# senproj_final.net
KiCad netlist of a schematic drawn in EAGLE
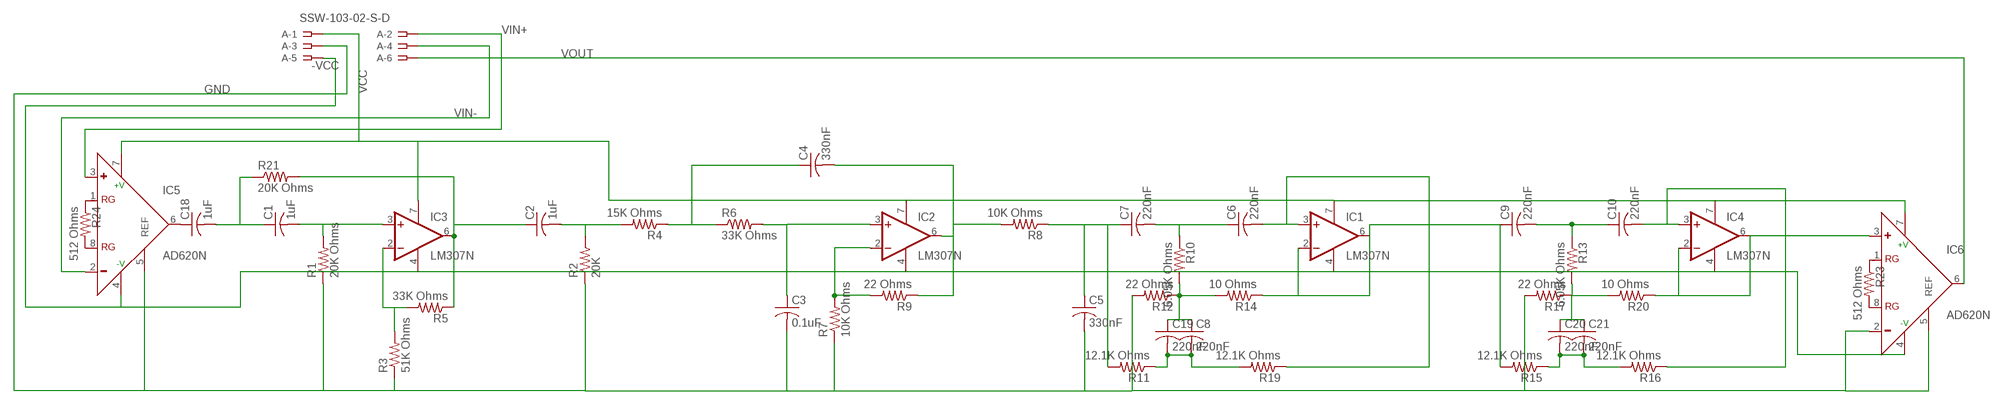
[diagram p0: schematic, sheet 1]

(export (version "E")
  (design (tool "Eeschema 10.0.6"))
  (components
    (comp (ref "A")
      (value "SSW-103-02-S-D")
      (footprint "eagle-import:SSW-103-02-S-D")
      (libsource (lib "eagle-import") (part "SSW-103-02-S-D"))
    )
    (comp (ref "C1")
      (value "1uF")
      (footprint "eagle-import:C150-054X183")
      (libsource (lib "eagle-import") (part "C-US150-054X183"))
    )
    (comp (ref "C2")
      (value "1uF")
      (footprint "eagle-import:C150-054X183")
      (libsource (lib "eagle-import") (part "C-US150-054X183"))
    )
    (comp (ref "C3")
      (value "0.1uF")
      (footprint "eagle-import:C075-032X103")
      (libsource (lib "eagle-import") (part "C-US075-032X103"))
    )
    (comp (ref "C4")
      (value "330nF")
      (footprint "eagle-import:C102-043X133")
      (libsource (lib "eagle-import") (part "C-US102-043X133"))
    )
    (comp (ref "C5")
      (value "330nF")
      (footprint "eagle-import:C102-043X133")
      (libsource (lib "eagle-import") (part "C-US102-043X133"))
    )
    (comp (ref "C6")
      (value "220nF")
      (footprint "eagle-import:C050-024X044")
      (libsource (lib "eagle-import") (part "C-US050-024X044"))
    )
    (comp (ref "C7")
      (value "220nF")
      (footprint "eagle-import:C050-024X044")
      (libsource (lib "eagle-import") (part "C-US050-024X044"))
    )
    (comp (ref "C8")
      (value "220nF")
      (footprint "eagle-import:C050-024X044")
      (libsource (lib "eagle-import") (part "C-US050-024X044"))
    )
    (comp (ref "C9")
      (value "220nF")
      (footprint "eagle-import:C050-024X044")
      (libsource (lib "eagle-import") (part "C-US050-024X044"))
    )
    (comp (ref "C10")
      (value "220nF")
      (footprint "eagle-import:C050-024X044")
      (libsource (lib "eagle-import") (part "C-US050-024X044"))
    )
    (comp (ref "C18")
      (value "1uF")
      (footprint "eagle-import:C150-054X183")
      (libsource (lib "eagle-import") (part "C-US150-054X183"))
    )
    (comp (ref "C19")
      (value "220nF")
      (footprint "eagle-import:C050-024X044")
      (libsource (lib "eagle-import") (part "C-US050-024X044"))
    )
    (comp (ref "C20")
      (value "220nF")
      (footprint "eagle-import:C050-024X044")
      (libsource (lib "eagle-import") (part "C-US050-024X044"))
    )
    (comp (ref "C21")
      (value "220nF")
      (footprint "eagle-import:C050-024X044")
      (libsource (lib "eagle-import") (part "C-US050-024X044"))
    )
    (comp (ref "IC1")
      (value "LM307N")
      (footprint "eagle-import:DIL08")
      (libsource (lib "eagle-import") (part "LM307N"))
    )
    (comp (ref "IC2")
      (value "LM307N")
      (footprint "eagle-import:DIL08")
      (libsource (lib "eagle-import") (part "LM307N"))
    )
    (comp (ref "IC3")
      (value "LM307N")
      (footprint "eagle-import:DIL08")
      (libsource (lib "eagle-import") (part "LM307N"))
    )
    (comp (ref "IC4")
      (value "LM307N")
      (footprint "eagle-import:DIL08")
      (libsource (lib "eagle-import") (part "LM307N"))
    )
    (comp (ref "IC5")
      (value "AD620N")
      (footprint "eagle-import:DIL08")
      (fields (field (name "MF") "ALTERA CORPORATION") (field (name "MPN") "AD620AN"))
      (libsource (lib "eagle-import") (part "AD620N"))
    )
    (comp (ref "IC6")
      (value "AD620N")
      (footprint "eagle-import:DIL08")
      (fields (field (name "MF") "ALTERA CORPORATION") (field (name "MPN") "AD620AN"))
      (libsource (lib "eagle-import") (part "AD620N"))
    )
    (comp (ref "R1")
      (value "20K Ohms")
      (footprint "eagle-import:0204_7")
      (libsource (lib "eagle-import") (part "R-US_0204/7"))
    )
    (comp (ref "R2")
      (value "20K")
      (footprint "eagle-import:0204_7")
      (libsource (lib "eagle-import") (part "R-US_0204/7"))
    )
    (comp (ref "R3")
      (value "51K Ohms")
      (footprint "eagle-import:0204_7")
      (libsource (lib "eagle-import") (part "R-US_0204/7"))
    )
    (comp (ref "R4")
      (value "15K Ohms")
      (footprint "eagle-import:0204_7")
      (libsource (lib "eagle-import") (part "R-US_0204/7"))
    )
    (comp (ref "R5")
      (value "33K Ohms")
      (footprint "eagle-import:0204_7")
      (libsource (lib "eagle-import") (part "R-US_0204/7"))
    )
    (comp (ref "R6")
      (value "33K Ohms")
      (footprint "eagle-import:0204_7")
      (libsource (lib "eagle-import") (part "R-US_0204/7"))
    )
    (comp (ref "R7")
      (value "10K Ohms")
      (footprint "eagle-import:0204_7")
      (libsource (lib "eagle-import") (part "R-US_0204/7"))
    )
    (comp (ref "R8")
      (value "10K Ohms")
      (footprint "eagle-import:0204_7")
      (libsource (lib "eagle-import") (part "R-US_0204/7"))
    )
    (comp (ref "R9")
      (value "22 Ohms")
      (footprint "eagle-import:0204_7")
      (libsource (lib "eagle-import") (part "R-US_0204/7"))
    )
    (comp (ref "R10")
      (value "6.05K Ohms")
      (footprint "eagle-import:0204_7")
      (libsource (lib "eagle-import") (part "R-US_0204/7"))
    )
    (comp (ref "R11")
      (value "12.1K Ohms")
      (footprint "eagle-import:0204_7")
      (libsource (lib "eagle-import") (part "R-US_0204/7"))
    )
    (comp (ref "R12")
      (value "22 Ohms")
      (footprint "eagle-import:0204_7")
      (libsource (lib "eagle-import") (part "R-US_0204/7"))
    )
    (comp (ref "R13")
      (value "6.05K Ohms")
      (footprint "eagle-import:0204_7")
      (libsource (lib "eagle-import") (part "R-US_0204/7"))
    )
    (comp (ref "R14")
      (value "10 Ohms")
      (footprint "eagle-import:0204_7")
      (libsource (lib "eagle-import") (part "R-US_0204/7"))
    )
    (comp (ref "R15")
      (value "12.1K Ohms")
      (footprint "eagle-import:0204_7")
      (libsource (lib "eagle-import") (part "R-US_0204/7"))
    )
    (comp (ref "R16")
      (value "12.1K Ohms")
      (footprint "eagle-import:0204_7")
      (libsource (lib "eagle-import") (part "R-US_0204/7"))
    )
    (comp (ref "R17")
      (value "22 Ohms")
      (footprint "eagle-import:0204_7")
      (libsource (lib "eagle-import") (part "R-US_0204/7"))
    )
    (comp (ref "R19")
      (value "12.1K Ohms")
      (footprint "eagle-import:0204_7")
      (libsource (lib "eagle-import") (part "R-US_0204/7"))
    )
    (comp (ref "R20")
      (value "10 Ohms")
      (footprint "eagle-import:0204_7")
      (libsource (lib "eagle-import") (part "R-US_0204/7"))
    )
    (comp (ref "R21")
      (value "20K Ohms")
      (footprint "eagle-import:0204_7")
      (libsource (lib "eagle-import") (part "R-US_0204/7"))
    )
    (comp (ref "R23")
      (value "512 Ohms")
      (footprint "eagle-import:0204_7")
      (libsource (lib "eagle-import") (part "R-US_0204/7"))
    )
    (comp (ref "R24")
      (value "512 Ohms")
      (footprint "eagle-import:0204_7")
      (libsource (lib "eagle-import") (part "R-US_0204/7"))
    )
  )
  (nets
    (net (code "1") (name "/-VCC") (class "Default")
      (node (ref "A") (pin "5") (pinfunction "1_5") (pintype "passive"))
      (node (ref "IC1") (pin "4") (pinfunction "V-_4") (pintype "power_in"))
      (node (ref "IC2") (pin "4") (pinfunction "V-_4") (pintype "power_in"))
      (node (ref "IC3") (pin "4") (pinfunction "V-_4") (pintype "power_in"))
      (node (ref "IC4") (pin "4") (pinfunction "V-_4") (pintype "power_in"))
      (node (ref "IC5") (pin "4") (pinfunction "-V_4") (pintype "power_in"))
      (node (ref "IC6") (pin "4") (pinfunction "-V_4") (pintype "power_in"))
    )
    (net (code "2") (name "/GND") (class "Default")
      (node (ref "A") (pin "3") (pinfunction "1_3") (pintype "passive"))
      (node (ref "C3") (pin "2") (pinfunction "2_2") (pintype "passive"))
      (node (ref "C5") (pin "2") (pinfunction "2_2") (pintype "passive"))
      (node (ref "IC5") (pin "5") (pinfunction "REF_5") (pintype "passive"))
      (node (ref "IC6") (pin "2") (pinfunction "-_2") (pintype "input"))
      (node (ref "IC6") (pin "5") (pinfunction "REF_5") (pintype "passive"))
      (node (ref "R1") (pin "1") (pinfunction "1_1") (pintype "passive"))
      (node (ref "R12") (pin "2") (pinfunction "2_2") (pintype "passive"))
      (node (ref "R17") (pin "2") (pinfunction "2_2") (pintype "passive"))
      (node (ref "R2") (pin "1") (pinfunction "1_1") (pintype "passive"))
      (node (ref "R3") (pin "1") (pinfunction "1_1") (pintype "passive"))
      (node (ref "R7") (pin "1") (pinfunction "1_1") (pintype "passive"))
    )
    (net (code "3") (name "/VCC") (class "Default")
      (node (ref "A") (pin "1") (pinfunction "1_1") (pintype "passive"))
      (node (ref "IC1") (pin "7") (pinfunction "V+_7") (pintype "power_in"))
      (node (ref "IC2") (pin "7") (pinfunction "V+_7") (pintype "power_in"))
      (node (ref "IC3") (pin "7") (pinfunction "V+_7") (pintype "power_in"))
      (node (ref "IC4") (pin "7") (pinfunction "V+_7") (pintype "power_in"))
      (node (ref "IC5") (pin "7") (pinfunction "+V_7") (pintype "power_in"))
      (node (ref "IC6") (pin "7") (pinfunction "+V_7") (pintype "power_in"))
    )
    (net (code "4") (name "/VIN+") (class "Default")
      (node (ref "A") (pin "2") (pinfunction "1_2") (pintype "passive"))
      (node (ref "IC5") (pin "3") (pinfunction "+_3") (pintype "input"))
    )
    (net (code "5") (name "/VIN-") (class "Default")
      (node (ref "A") (pin "4") (pinfunction "1_4") (pintype "passive"))
      (node (ref "IC5") (pin "2") (pinfunction "-_2") (pintype "input"))
    )
    (net (code "6") (name "/VOUT") (class "Default")
      (node (ref "A") (pin "6") (pinfunction "1_6") (pintype "passive"))
      (node (ref "IC6") (pin "6") (pinfunction "OUT_6") (pintype "output"))
    )
    (net (code "7") (name "Net-(C1-Pad1)") (class "Default")
      (node (ref "C1") (pin "1") (pinfunction "1_1") (pintype "passive"))
      (node (ref "C18") (pin "2") (pinfunction "2_2") (pintype "passive"))
      (node (ref "R21") (pin "1") (pinfunction "1_1") (pintype "passive"))
    )
    (net (code "8") (name "Net-(C2-Pad2)") (class "Default")
      (node (ref "C2") (pin "2") (pinfunction "2_2") (pintype "passive"))
      (node (ref "R2") (pin "2") (pinfunction "2_2") (pintype "passive"))
      (node (ref "R4") (pin "2") (pinfunction "2_2") (pintype "passive"))
    )
    (net (code "9") (name "Net-(C4-Pad1)") (class "Default")
      (node (ref "C4") (pin "1") (pinfunction "1_1") (pintype "passive"))
      (node (ref "R4") (pin "1") (pinfunction "1_1") (pintype "passive"))
      (node (ref "R6") (pin "1") (pinfunction "1_1") (pintype "passive"))
    )
    (net (code "10") (name "Net-(C5-Pad1)") (class "Default")
      (node (ref "C5") (pin "1") (pinfunction "1_1") (pintype "passive"))
      (node (ref "C7") (pin "1") (pinfunction "1_1") (pintype "passive"))
      (node (ref "R11") (pin "2") (pinfunction "2_2") (pintype "passive"))
      (node (ref "R8") (pin "1") (pinfunction "1_1") (pintype "passive"))
    )
    (net (code "11") (name "Net-(C6-Pad1)") (class "Default")
      (node (ref "C6") (pin "1") (pinfunction "1_1") (pintype "passive"))
      (node (ref "C7") (pin "2") (pinfunction "2_2") (pintype "passive"))
      (node (ref "R10") (pin "1") (pinfunction "1_1") (pintype "passive"))
    )
    (net (code "12") (name "Net-(C10-Pad1)") (class "Default")
      (node (ref "C10") (pin "1") (pinfunction "1_1") (pintype "passive"))
      (node (ref "C9") (pin "2") (pinfunction "2_2") (pintype "passive"))
      (node (ref "R13") (pin "1") (pinfunction "1_1") (pintype "passive"))
    )
    (net (code "13") (name "Net-(C19-Pad1)") (class "Default")
      (node (ref "C19") (pin "1") (pinfunction "1_1") (pintype "passive"))
      (node (ref "C8") (pin "1") (pinfunction "1_1") (pintype "passive"))
      (node (ref "R10") (pin "2") (pinfunction "2_2") (pintype "passive"))
      (node (ref "R12") (pin "1") (pinfunction "1_1") (pintype "passive"))
      (node (ref "R14") (pin "2") (pinfunction "2_2") (pintype "passive"))
    )
    (net (code "14") (name "Net-(C19-Pad2)") (class "Default")
      (node (ref "C19") (pin "2") (pinfunction "2_2") (pintype "passive"))
      (node (ref "C8") (pin "2") (pinfunction "2_2") (pintype "passive"))
      (node (ref "R11") (pin "1") (pinfunction "1_1") (pintype "passive"))
      (node (ref "R19") (pin "2") (pinfunction "2_2") (pintype "passive"))
    )
    (net (code "15") (name "Net-(C20-Pad1)") (class "Default")
      (node (ref "C20") (pin "1") (pinfunction "1_1") (pintype "passive"))
      (node (ref "C21") (pin "1") (pinfunction "1_1") (pintype "passive"))
      (node (ref "R13") (pin "2") (pinfunction "2_2") (pintype "passive"))
      (node (ref "R17") (pin "1") (pinfunction "1_1") (pintype "passive"))
      (node (ref "R20") (pin "2") (pinfunction "2_2") (pintype "passive"))
    )
    (net (code "16") (name "Net-(C20-Pad2)") (class "Default")
      (node (ref "C20") (pin "2") (pinfunction "2_2") (pintype "passive"))
      (node (ref "C21") (pin "2") (pinfunction "2_2") (pintype "passive"))
      (node (ref "R15") (pin "1") (pinfunction "1_1") (pintype "passive"))
      (node (ref "R16") (pin "2") (pinfunction "2_2") (pintype "passive"))
    )
    (net (code "17") (name "Net-(IC1-+IN)") (class "Default")
      (node (ref "C6") (pin "2") (pinfunction "2_2") (pintype "passive"))
      (node (ref "IC1") (pin "3") (pinfunction "+IN_3") (pintype "input"))
      (node (ref "R19") (pin "1") (pinfunction "1_1") (pintype "passive"))
    )
    (net (code "18") (name "Net-(IC1--IN)") (class "Default")
      (node (ref "C9") (pin "1") (pinfunction "1_1") (pintype "passive"))
      (node (ref "IC1") (pin "2") (pinfunction "-IN_2") (pintype "input"))
      (node (ref "IC1") (pin "6") (pinfunction "OUT_6") (pintype "output"))
      (node (ref "R14") (pin "1") (pinfunction "1_1") (pintype "passive"))
      (node (ref "R15") (pin "2") (pinfunction "2_2") (pintype "passive"))
    )
    (net (code "19") (name "Net-(IC2-+IN)") (class "Default")
      (node (ref "C3") (pin "1") (pinfunction "1_1") (pintype "passive"))
      (node (ref "IC2") (pin "3") (pinfunction "+IN_3") (pintype "input"))
      (node (ref "R6") (pin "2") (pinfunction "2_2") (pintype "passive"))
    )
    (net (code "20") (name "Net-(IC2--IN)") (class "Default")
      (node (ref "IC2") (pin "2") (pinfunction "-IN_2") (pintype "input"))
      (node (ref "R7") (pin "2") (pinfunction "2_2") (pintype "passive"))
      (node (ref "R9") (pin "2") (pinfunction "2_2") (pintype "passive"))
    )
    (net (code "21") (name "Net-(IC2-OUT)") (class "Default")
      (node (ref "C4") (pin "2") (pinfunction "2_2") (pintype "passive"))
      (node (ref "IC2") (pin "6") (pinfunction "OUT_6") (pintype "output"))
      (node (ref "R8") (pin "2") (pinfunction "2_2") (pintype "passive"))
      (node (ref "R9") (pin "1") (pinfunction "1_1") (pintype "passive"))
    )
    (net (code "22") (name "Net-(IC3-+IN)") (class "Default")
      (node (ref "C1") (pin "2") (pinfunction "2_2") (pintype "passive"))
      (node (ref "IC3") (pin "3") (pinfunction "+IN_3") (pintype "input"))
      (node (ref "R1") (pin "2") (pinfunction "2_2") (pintype "passive"))
    )
    (net (code "23") (name "Net-(IC3--IN)") (class "Default")
      (node (ref "IC3") (pin "2") (pinfunction "-IN_2") (pintype "input"))
      (node (ref "R3") (pin "2") (pinfunction "2_2") (pintype "passive"))
      (node (ref "R5") (pin "2") (pinfunction "2_2") (pintype "passive"))
    )
    (net (code "24") (name "Net-(IC3-OUT)") (class "Default")
      (node (ref "C2") (pin "1") (pinfunction "1_1") (pintype "passive"))
      (node (ref "IC3") (pin "6") (pinfunction "OUT_6") (pintype "output"))
      (node (ref "R21") (pin "2") (pinfunction "2_2") (pintype "passive"))
      (node (ref "R5") (pin "1") (pinfunction "1_1") (pintype "passive"))
    )
    (net (code "25") (name "Net-(IC4-+IN)") (class "Default")
      (node (ref "C10") (pin "2") (pinfunction "2_2") (pintype "passive"))
      (node (ref "IC4") (pin "3") (pinfunction "+IN_3") (pintype "input"))
      (node (ref "R16") (pin "1") (pinfunction "1_1") (pintype "passive"))
    )
    (net (code "26") (name "Net-(IC4--IN)") (class "Default")
      (node (ref "IC4") (pin "2") (pinfunction "-IN_2") (pintype "input"))
      (node (ref "IC4") (pin "6") (pinfunction "OUT_6") (pintype "output"))
      (node (ref "IC6") (pin "3") (pinfunction "+_3") (pintype "input"))
      (node (ref "R20") (pin "1") (pinfunction "1_1") (pintype "passive"))
    )
    (net (code "27") (name "Net-(IC5-OUT)") (class "Default")
      (node (ref "C18") (pin "1") (pinfunction "1_1") (pintype "passive"))
      (node (ref "IC5") (pin "6") (pinfunction "OUT_6") (pintype "output"))
    )
    (net (code "28") (name "Net-(IC5-RG-Pad1)") (class "Default")
      (node (ref "IC5") (pin "1") (pinfunction "RG_1") (pintype "passive"))
      (node (ref "R24") (pin "1") (pinfunction "1_1") (pintype "passive"))
    )
    (net (code "29") (name "Net-(IC5-RG-Pad8)") (class "Default")
      (node (ref "IC5") (pin "8") (pinfunction "RG_8") (pintype "passive"))
      (node (ref "R24") (pin "2") (pinfunction "2_2") (pintype "passive"))
    )
    (net (code "30") (name "Net-(IC6-RG-Pad1)") (class "Default")
      (node (ref "IC6") (pin "1") (pinfunction "RG_1") (pintype "passive"))
      (node (ref "R23") (pin "1") (pinfunction "1_1") (pintype "passive"))
    )
    (net (code "31") (name "Net-(IC6-RG-Pad8)") (class "Default")
      (node (ref "IC6") (pin "8") (pinfunction "RG_8") (pintype "passive"))
      (node (ref "R23") (pin "2") (pinfunction "2_2") (pintype "passive"))
    )
  )
)
